# mainboard.net
KiCad netlist of a schematic drawn in EAGLE
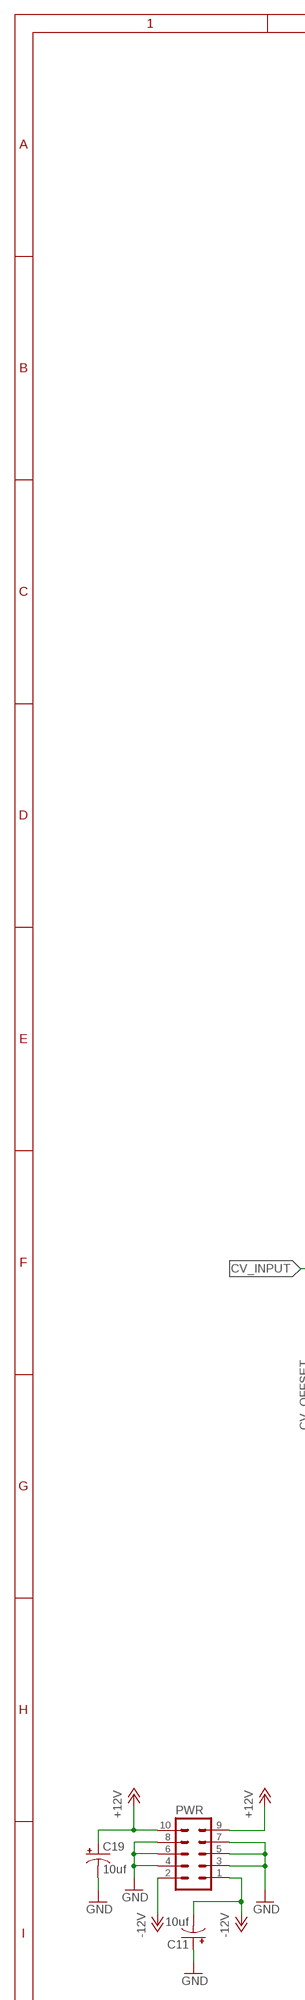
[diagram p0: schematic, sheet 1, part 1 of 2]
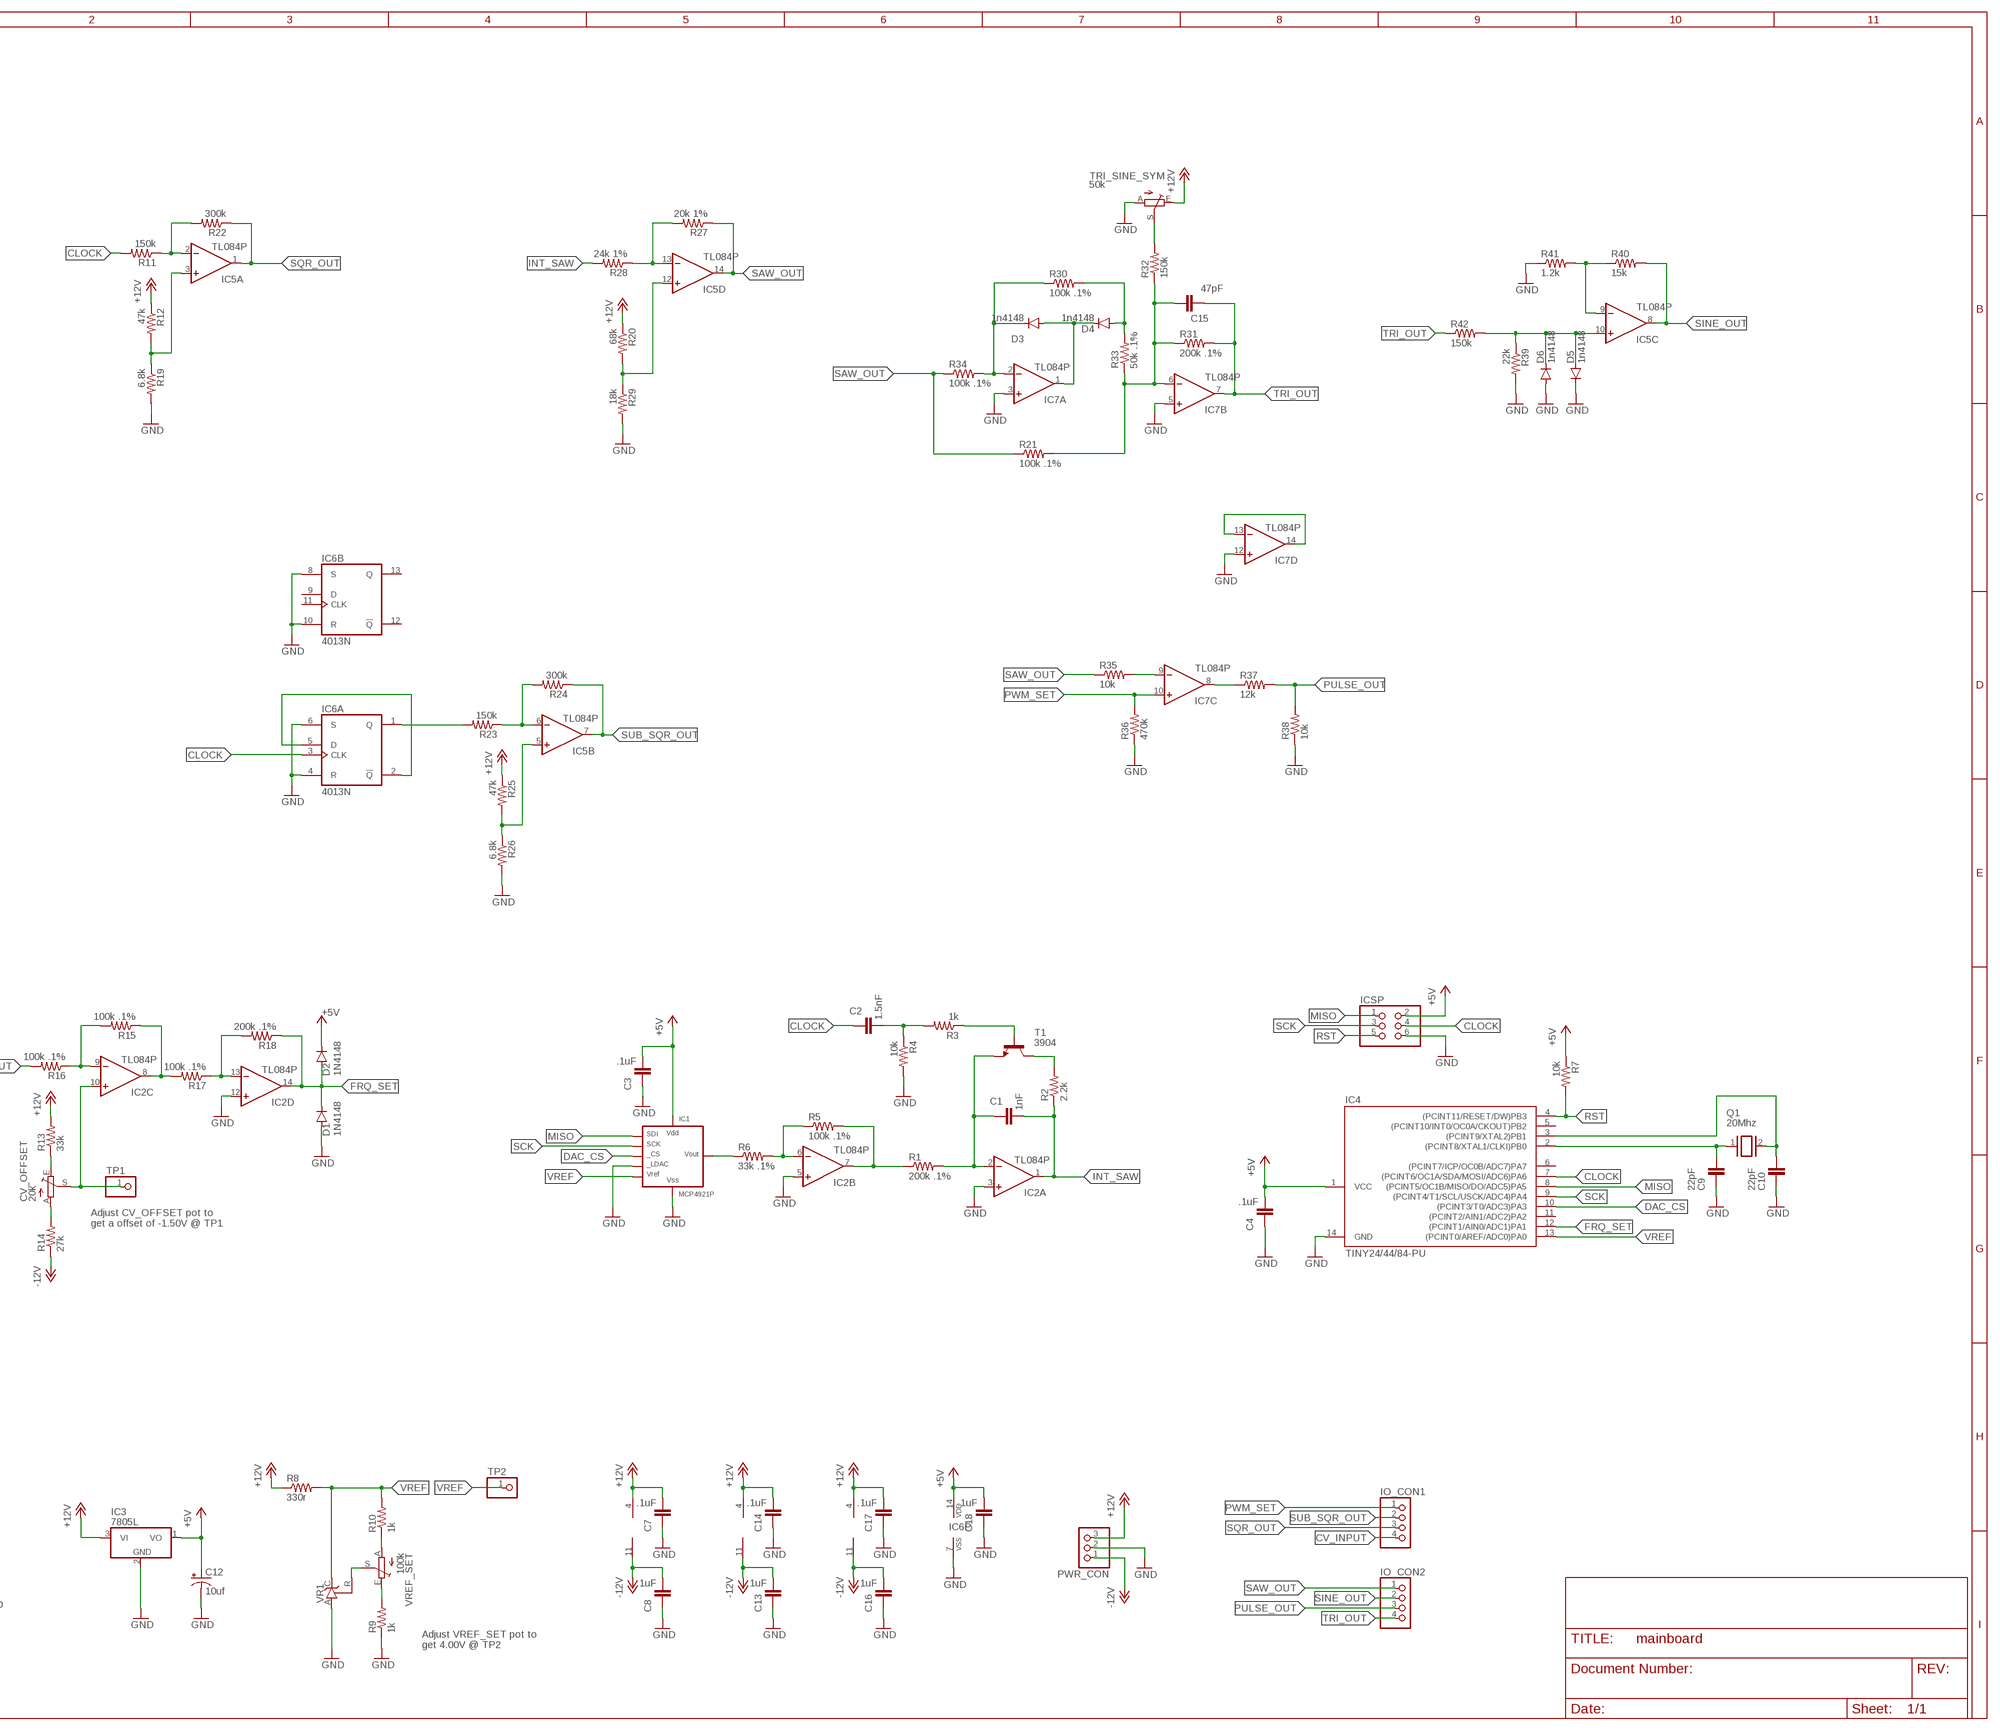
[diagram p1: schematic, sheet 1, part 2 of 2]

(export (version "E")
  (design (tool "Eeschema 10.0.6"))
  (components
    (comp (ref "C1")
      (value "1nF")
      (footprint "eagle-import:C050-025X075")
      (libsource (lib "eagle-import") (part "C-EU050-025X075"))
    )
    (comp (ref "C2")
      (value "1.5nF")
      (footprint "eagle-import:C050-024X044")
      (libsource (lib "eagle-import") (part "C-EU050-024X044"))
    )
    (comp (ref "C3")
      (value ".1uF")
      (footprint "eagle-import:C050-024X044")
      (libsource (lib "eagle-import") (part "C-EU050-024X044"))
    )
    (comp (ref "C4")
      (value ".1uF")
      (footprint "eagle-import:C050-024X044")
      (libsource (lib "eagle-import") (part "C-EU050-024X044"))
    )
    (comp (ref "C7")
      (value ".1uF")
      (footprint "eagle-import:C050-024X044")
      (libsource (lib "eagle-import") (part "C-EU050-024X044"))
    )
    (comp (ref "C8")
      (value ".1uF")
      (footprint "eagle-import:C050-024X044")
      (libsource (lib "eagle-import") (part "C-EU050-024X044"))
    )
    (comp (ref "C9")
      (value "22pF")
      (footprint "eagle-import:C050-024X044")
      (libsource (lib "eagle-import") (part "C-EU050-024X044"))
    )
    (comp (ref "C10")
      (value "22pF")
      (footprint "eagle-import:C050-024X044")
      (libsource (lib "eagle-import") (part "C-EU050-024X044"))
    )
    (comp (ref "C11")
      (value "10uf")
      (footprint "eagle-import:E2,5-5")
      (libsource (lib "eagle-import") (part "CPOL-USE2.5-5"))
    )
    (comp (ref "C12")
      (value "10uf")
      (footprint "eagle-import:E2,5-5")
      (libsource (lib "eagle-import") (part "CPOL-USE2.5-5"))
    )
    (comp (ref "C13")
      (value ".1uF")
      (footprint "eagle-import:C050-024X044")
      (libsource (lib "eagle-import") (part "C-EU050-024X044"))
    )
    (comp (ref "C14")
      (value ".1uF")
      (footprint "eagle-import:C050-024X044")
      (libsource (lib "eagle-import") (part "C-EU050-024X044"))
    )
    (comp (ref "C15")
      (value "47pF")
      (footprint "eagle-import:C050-024X044")
      (libsource (lib "eagle-import") (part "C-EU050-024X044"))
    )
    (comp (ref "C16")
      (value ".1uF")
      (footprint "eagle-import:C050-024X044")
      (libsource (lib "eagle-import") (part "C-EU050-024X044"))
    )
    (comp (ref "C17")
      (value ".1uF")
      (footprint "eagle-import:C050-024X044")
      (libsource (lib "eagle-import") (part "C-EU050-024X044"))
    )
    (comp (ref "C18")
      (value ".1uF")
      (footprint "eagle-import:C050-024X044")
      (libsource (lib "eagle-import") (part "C-EU050-024X044"))
    )
    (comp (ref "C19")
      (value "10uf")
      (footprint "eagle-import:E2,5-5")
      (libsource (lib "eagle-import") (part "CPOL-USE2.5-5"))
    )
    (comp (ref "CV_OFFSET")
      (value "20k")
      (footprint "eagle-import:S64YW")
      (libsource (lib "eagle-import") (part "TRIM_1234-S64YW"))
    )
    (comp (ref "D1")
      (value "1N4148")
      (footprint "eagle-import:DO35-7")
      (libsource (lib "eagle-import") (part "1N4148DO35-7"))
    )
    (comp (ref "D2")
      (value "1N4148")
      (footprint "eagle-import:DO35-7")
      (libsource (lib "eagle-import") (part "1N4148DO35-7"))
    )
    (comp (ref "D3")
      (value "1n4148")
      (footprint "eagle-import:DO35-7")
      (libsource (lib "eagle-import") (part "1N4148DO35-7"))
    )
    (comp (ref "D4")
      (value "1n4148")
      (footprint "eagle-import:DO35-7")
      (libsource (lib "eagle-import") (part "1N4148DO35-7"))
    )
    (comp (ref "D5")
      (value "1n4148")
      (footprint "eagle-import:DO35-7")
      (libsource (lib "eagle-import") (part "1N4148DO35-7"))
    )
    (comp (ref "D6")
      (value "1n4148")
      (footprint "eagle-import:DO35-7")
      (libsource (lib "eagle-import") (part "1N4148DO35-7"))
    )
    (comp (ref "IC1")
      (value "MCP4921P")
      (footprint "eagle-import:DIL8")
      (libsource (lib "eagle-import") (part "MCP4921P"))
    )
    (comp (ref "IC2")
      (value "TL084P")
      (footprint "eagle-import:DIL14")
      (libsource (lib "eagle-import") (part "TL084P"))
    )
    (comp (ref "IC3")
      (value "7805L")
      (footprint "eagle-import:TO92")
      (libsource (lib "eagle-import") (part "78L05"))
    )
    (comp (ref "IC4")
      (value "TINY24/44/84-PU")
      (footprint "eagle-import:DIL14")
      (libsource (lib "eagle-import") (part "TINY24/44/84-PU"))
    )
    (comp (ref "IC5")
      (value "TL084P")
      (footprint "eagle-import:DIL14")
      (libsource (lib "eagle-import") (part "TL084P"))
    )
    (comp (ref "IC6")
      (value "4013N")
      (footprint "eagle-import:DIL14")
      (libsource (lib "eagle-import") (part "4013N"))
    )
    (comp (ref "IC7")
      (value "TL084P")
      (footprint "eagle-import:DIL14")
      (libsource (lib "eagle-import") (part "TL084P"))
    )
    (comp (ref "ICSP")
      (value "PINHD-2X3")
      (footprint "eagle-import:2X03")
      (libsource (lib "eagle-import") (part "PINHD-2X3"))
    )
    (comp (ref "IO_CON1")
      (value "PINHD-1X4")
      (footprint "eagle-import:1X04")
      (libsource (lib "eagle-import") (part "PINHD-1X4"))
    )
    (comp (ref "IO_CON2")
      (value "PINHD-1X4")
      (footprint "eagle-import:1X04")
      (libsource (lib "eagle-import") (part "PINHD-1X4"))
    )
    (comp (ref "PWR")
      (value "ML10")
      (footprint "eagle-import:ML10")
      (libsource (lib "eagle-import") (part "ML10"))
    )
    (comp (ref "PWR_CON")
      (value "PINHD-1X3")
      (footprint "eagle-import:1X03")
      (libsource (lib "eagle-import") (part "PINHD-1X3"))
    )
    (comp (ref "Q1")
      (value "20Mhz")
      (footprint "eagle-import:QS")
      (libsource (lib "eagle-import") (part "XTAL/S"))
    )
    (comp (ref "R1")
      (value "200k .1%")
      (footprint "eagle-import:0207_7")
      (libsource (lib "eagle-import") (part "R-US_0207/7"))
    )
    (comp (ref "R2")
      (value "2.2k")
      (footprint "eagle-import:0207_7")
      (libsource (lib "eagle-import") (part "R-US_0207/7"))
    )
    (comp (ref "R3")
      (value "1k")
      (footprint "eagle-import:0207_7")
      (libsource (lib "eagle-import") (part "R-US_0207/7"))
    )
    (comp (ref "R4")
      (value "10k")
      (footprint "eagle-import:0207_7")
      (libsource (lib "eagle-import") (part "R-US_0207/7"))
    )
    (comp (ref "R5")
      (value "100k .1%")
      (footprint "eagle-import:0207_7")
      (libsource (lib "eagle-import") (part "R-US_0207/7"))
    )
    (comp (ref "R6")
      (value "33k .1%")
      (footprint "eagle-import:0207_7")
      (libsource (lib "eagle-import") (part "R-US_0207/7"))
    )
    (comp (ref "R7")
      (value "10k")
      (footprint "eagle-import:0207_7")
      (libsource (lib "eagle-import") (part "R-US_0207/7"))
    )
    (comp (ref "R8")
      (value "330r")
      (footprint "eagle-import:0207_7")
      (libsource (lib "eagle-import") (part "R-US_0207/7"))
    )
    (comp (ref "R9")
      (value "1k")
      (footprint "eagle-import:0207_7")
      (libsource (lib "eagle-import") (part "R-US_0207/7"))
    )
    (comp (ref "R10")
      (value "1k")
      (footprint "eagle-import:0207_7")
      (libsource (lib "eagle-import") (part "R-US_0207/7"))
    )
    (comp (ref "R11")
      (value "150k")
      (footprint "eagle-import:0207_7")
      (libsource (lib "eagle-import") (part "R-US_0207/7"))
    )
    (comp (ref "R12")
      (value "47k")
      (footprint "eagle-import:0207_7")
      (libsource (lib "eagle-import") (part "R-US_0207/7"))
    )
    (comp (ref "R13")
      (value "33k")
      (footprint "eagle-import:0207_7")
      (libsource (lib "eagle-import") (part "R-US_0207/7"))
    )
    (comp (ref "R14")
      (value "27k")
      (footprint "eagle-import:0207_7")
      (libsource (lib "eagle-import") (part "R-US_0207/7"))
    )
    (comp (ref "R15")
      (value "100k .1%")
      (footprint "eagle-import:0207_7")
      (libsource (lib "eagle-import") (part "R-US_0207/7"))
    )
    (comp (ref "R16")
      (value "100k .1%")
      (footprint "eagle-import:0207_7")
      (libsource (lib "eagle-import") (part "R-US_0207/7"))
    )
    (comp (ref "R17")
      (value "100k .1%")
      (footprint "eagle-import:0207_7")
      (libsource (lib "eagle-import") (part "R-US_0207/7"))
    )
    (comp (ref "R18")
      (value "200k .1%")
      (footprint "eagle-import:0207_7")
      (libsource (lib "eagle-import") (part "R-US_0207/7"))
    )
    (comp (ref "R19")
      (value "6.8k")
      (footprint "eagle-import:0207_7")
      (libsource (lib "eagle-import") (part "R-US_0207/7"))
    )
    (comp (ref "R20")
      (value "68k")
      (footprint "eagle-import:0207_7")
      (libsource (lib "eagle-import") (part "R-US_0207/7"))
    )
    (comp (ref "R21")
      (value "100k .1%")
      (footprint "eagle-import:0207_7")
      (libsource (lib "eagle-import") (part "R-US_0207/7"))
    )
    (comp (ref "R22")
      (value "300k")
      (footprint "eagle-import:0207_7")
      (libsource (lib "eagle-import") (part "R-US_0207/7"))
    )
    (comp (ref "R23")
      (value "150k")
      (footprint "eagle-import:0207_7")
      (libsource (lib "eagle-import") (part "R-US_0207/7"))
    )
    (comp (ref "R24")
      (value "300k")
      (footprint "eagle-import:0207_7")
      (libsource (lib "eagle-import") (part "R-US_0207/7"))
    )
    (comp (ref "R25")
      (value "47k")
      (footprint "eagle-import:0207_7")
      (libsource (lib "eagle-import") (part "R-US_0207/7"))
    )
    (comp (ref "R26")
      (value "6.8k")
      (footprint "eagle-import:0207_7")
      (libsource (lib "eagle-import") (part "R-US_0207/7"))
    )
    (comp (ref "R27")
      (value "20k 1%")
      (footprint "eagle-import:0207_7")
      (libsource (lib "eagle-import") (part "R-US_0207/7"))
    )
    (comp (ref "R28")
      (value "24k 1%")
      (footprint "eagle-import:0207_7")
      (libsource (lib "eagle-import") (part "R-US_0207/7"))
    )
    (comp (ref "R29")
      (value "18k")
      (footprint "eagle-import:0207_7")
      (libsource (lib "eagle-import") (part "R-US_0207/7"))
    )
    (comp (ref "R30")
      (value "100k .1%")
      (footprint "eagle-import:0207_7")
      (libsource (lib "eagle-import") (part "R-US_0207/7"))
    )
    (comp (ref "R31")
      (value "200k .1%")
      (footprint "eagle-import:0207_7")
      (libsource (lib "eagle-import") (part "R-US_0207/7"))
    )
    (comp (ref "R32")
      (value "150k")
      (footprint "eagle-import:0207_7")
      (libsource (lib "eagle-import") (part "R-US_0207/7"))
    )
    (comp (ref "R33")
      (value "50k .1%")
      (footprint "eagle-import:0207_7")
      (libsource (lib "eagle-import") (part "R-US_0207/7"))
    )
    (comp (ref "R34")
      (value "100k .1%")
      (footprint "eagle-import:0207_7")
      (libsource (lib "eagle-import") (part "R-US_0207/7"))
    )
    (comp (ref "R35")
      (value "10k")
      (footprint "eagle-import:0207_7")
      (libsource (lib "eagle-import") (part "R-US_0207/7"))
    )
    (comp (ref "R36")
      (value "470k")
      (footprint "eagle-import:0207_7")
      (libsource (lib "eagle-import") (part "R-US_0207/7"))
    )
    (comp (ref "R37")
      (value "12k")
      (footprint "eagle-import:0207_7")
      (libsource (lib "eagle-import") (part "R-US_0207/7"))
    )
    (comp (ref "R38")
      (value "10k")
      (footprint "eagle-import:0207_7")
      (libsource (lib "eagle-import") (part "R-US_0207/7"))
    )
    (comp (ref "R39")
      (value "22k")
      (footprint "eagle-import:0207_7")
      (libsource (lib "eagle-import") (part "R-US_0207/7"))
    )
    (comp (ref "R40")
      (value "15k")
      (footprint "eagle-import:0207_7")
      (libsource (lib "eagle-import") (part "R-US_0207/7"))
    )
    (comp (ref "R41")
      (value "1.2k")
      (footprint "eagle-import:0207_7")
      (libsource (lib "eagle-import") (part "R-US_0207/7"))
    )
    (comp (ref "R42")
      (value "150k")
      (footprint "eagle-import:0207_7")
      (libsource (lib "eagle-import") (part "R-US_0207/7"))
    )
    (comp (ref "T1")
      (value "3904")
      (footprint "eagle-import:TO92-EBC")
      (libsource (lib "eagle-import") (part "-NPN-TO92-EBC2N3904"))
    )
    (comp (ref "TP1")
      (value "PINHD-1X1")
      (footprint "eagle-import:1X01")
      (libsource (lib "eagle-import") (part "PINHD-1X1"))
    )
    (comp (ref "TP2")
      (value "PINHD-1X1")
      (footprint "eagle-import:1X01")
      (libsource (lib "eagle-import") (part "PINHD-1X1"))
    )
    (comp (ref "TRI_SINE_SYM")
      (value "50k")
      (footprint "eagle-import:S64YW")
      (libsource (lib "eagle-import") (part "TRIM_1234-S64YW"))
    )
    (comp (ref "VR1")
      (value "TL431CLP")
      (footprint "eagle-import:TO92-CLP")
      (libsource (lib "eagle-import") (part "TL431CLP"))
    )
    (comp (ref "VREF_SET")
      (value "100k")
      (footprint "eagle-import:S64YW")
      (libsource (lib "eagle-import") (part "TRIM_1234-S64YW"))
    )
  )
  (nets
    (net (code "1") (name "+5V") (class "Default")
      (node (ref "C12") (pin "+") (pinfunction "+_+") (pintype "passive"))
      (node (ref "C18") (pin "2") (pinfunction "2_2") (pintype "passive"))
      (node (ref "C3") (pin "2") (pinfunction "2_2") (pintype "passive"))
      (node (ref "C4") (pin "2") (pinfunction "2_2") (pintype "passive"))
      (node (ref "D2") (pin "C") (pinfunction "C_C") (pintype "passive"))
      (node (ref "IC1") (pin "1") (pinfunction "VDD_1") (pintype "power_in"))
      (node (ref "IC3") (pin "1") (pinfunction "VO_1") (pintype "passive"))
      (node (ref "IC4") (pin "1") (pinfunction "VCC_1") (pintype "power_in"))
      (node (ref "IC6") (pin "14") (pinfunction "VDD_14") (pintype "power_in"))
      (node (ref "ICSP") (pin "2") (pinfunction "2_2") (pintype "passive"))
      (node (ref "R7") (pin "1") (pinfunction "1_1") (pintype "passive"))
    )
    (net (code "2") (name "+12V") (class "Default")
      (node (ref "C14") (pin "2") (pinfunction "2_2") (pintype "passive"))
      (node (ref "C17") (pin "2") (pinfunction "2_2") (pintype "passive"))
      (node (ref "C19") (pin "+") (pinfunction "+_+") (pintype "passive"))
      (node (ref "C7") (pin "2") (pinfunction "2_2") (pintype "passive"))
      (node (ref "IC2") (pin "4") (pinfunction "V+_4") (pintype "power_in"))
      (node (ref "IC3") (pin "3") (pinfunction "VI_3") (pintype "input"))
      (node (ref "IC5") (pin "4") (pinfunction "V+_4") (pintype "power_in"))
      (node (ref "IC7") (pin "4") (pinfunction "V+_4") (pintype "power_in"))
      (node (ref "PWR") (pin "10") (pinfunction "10_10") (pintype "passive"))
      (node (ref "PWR") (pin "9") (pinfunction "9_9") (pintype "passive"))
      (node (ref "PWR_CON") (pin "3") (pinfunction "3_3") (pintype "passive"))
      (node (ref "R12") (pin "1") (pinfunction "1_1") (pintype "passive"))
      (node (ref "R13") (pin "2") (pinfunction "2_2") (pintype "passive"))
      (node (ref "R20") (pin "1") (pinfunction "1_1") (pintype "passive"))
      (node (ref "R25") (pin "1") (pinfunction "1_1") (pintype "passive"))
      (node (ref "R8") (pin "1") (pinfunction "1_1") (pintype "passive"))
      (node (ref "TRI_SINE_SYM") (pin "E") (pinfunction "E_E") (pintype "passive"))
    )
    (net (code "3") (name "-12V") (class "Default")
      (node (ref "C11") (pin "-") (pinfunction "-_-") (pintype "passive"))
      (node (ref "C13") (pin "2") (pinfunction "2_2") (pintype "passive"))
      (node (ref "C16") (pin "2") (pinfunction "2_2") (pintype "passive"))
      (node (ref "C8") (pin "2") (pinfunction "2_2") (pintype "passive"))
      (node (ref "IC2") (pin "11") (pinfunction "V-_11") (pintype "power_in"))
      (node (ref "IC5") (pin "11") (pinfunction "V-_11") (pintype "power_in"))
      (node (ref "IC7") (pin "11") (pinfunction "V-_11") (pintype "power_in"))
      (node (ref "PWR") (pin "1") (pinfunction "1_1") (pintype "passive"))
      (node (ref "PWR") (pin "2") (pinfunction "2_2") (pintype "passive"))
      (node (ref "PWR_CON") (pin "1") (pinfunction "1_1") (pintype "passive"))
      (node (ref "R14") (pin "1") (pinfunction "1_1") (pintype "passive"))
    )
    (net (code "4") (name "CLOCK") (class "Default")
      (node (ref "C2") (pin "1") (pinfunction "1_1") (pintype "passive"))
      (node (ref "IC4") (pin "7") (pinfunction "(PCINT6/OC1A/SDA/MOSI/ADC6)PA6_7") (pintype "bidirectional"))
      (node (ref "IC6") (pin "3") (pinfunction "CLK_3") (pintype "input"))
      (node (ref "ICSP") (pin "4") (pinfunction "4_4") (pintype "passive"))
      (node (ref "R11") (pin "2") (pinfunction "2_2") (pintype "passive"))
    )
    (net (code "5") (name "CV_INPUT") (class "Default")
      (node (ref "IO_CON1") (pin "4") (pinfunction "4_4") (pintype "passive"))
      (node (ref "R16") (pin "2") (pinfunction "2_2") (pintype "passive"))
    )
    (net (code "6") (name "DAC_CS") (class "Default")
      (node (ref "IC1") (pin "2") (pinfunction "CS_2") (pintype "input"))
      (node (ref "IC4") (pin "10") (pinfunction "(PCINT3/T0/ADC3)PA3_10") (pintype "bidirectional"))
    )
    (net (code "7") (name "FRQ_SET") (class "Default")
      (node (ref "D1") (pin "C") (pinfunction "C_C") (pintype "passive"))
      (node (ref "D2") (pin "A") (pinfunction "A_A") (pintype "passive"))
      (node (ref "IC2") (pin "14") (pinfunction "OUT_14") (pintype "output"))
      (node (ref "IC4") (pin "12") (pinfunction "(PCINT1/AIN0/ADC1)PA1_12") (pintype "bidirectional"))
      (node (ref "R18") (pin "1") (pinfunction "1_1") (pintype "passive"))
    )
    (net (code "8") (name "GND") (class "Default")
      (node (ref "C10") (pin "1") (pinfunction "1_1") (pintype "passive"))
      (node (ref "C11") (pin "+") (pinfunction "+_+") (pintype "passive"))
      (node (ref "C12") (pin "-") (pinfunction "-_-") (pintype "passive"))
      (node (ref "C13") (pin "1") (pinfunction "1_1") (pintype "passive"))
      (node (ref "C14") (pin "1") (pinfunction "1_1") (pintype "passive"))
      (node (ref "C16") (pin "1") (pinfunction "1_1") (pintype "passive"))
      (node (ref "C17") (pin "1") (pinfunction "1_1") (pintype "passive"))
      (node (ref "C18") (pin "1") (pinfunction "1_1") (pintype "passive"))
      (node (ref "C19") (pin "-") (pinfunction "-_-") (pintype "passive"))
      (node (ref "C3") (pin "1") (pinfunction "1_1") (pintype "passive"))
      (node (ref "C4") (pin "1") (pinfunction "1_1") (pintype "passive"))
      (node (ref "C7") (pin "1") (pinfunction "1_1") (pintype "passive"))
      (node (ref "C8") (pin "1") (pinfunction "1_1") (pintype "passive"))
      (node (ref "C9") (pin "1") (pinfunction "1_1") (pintype "passive"))
      (node (ref "D1") (pin "A") (pinfunction "A_A") (pintype "passive"))
      (node (ref "D5") (pin "C") (pinfunction "C_C") (pintype "passive"))
      (node (ref "D6") (pin "A") (pinfunction "A_A") (pintype "passive"))
      (node (ref "IC1") (pin "5") (pinfunction "LDAC_5") (pintype "input"))
      (node (ref "IC1") (pin "7") (pinfunction "VSS_7") (pintype "power_in"))
      (node (ref "IC2") (pin "12") (pinfunction "+IN_12") (pintype "input"))
      (node (ref "IC2") (pin "3") (pinfunction "+IN_3") (pintype "input"))
      (node (ref "IC2") (pin "5") (pinfunction "+IN_5") (pintype "input"))
      (node (ref "IC3") (pin "2") (pinfunction "GND_2") (pintype "passive"))
      (node (ref "IC4") (pin "14") (pinfunction "GND_14") (pintype "power_in"))
      (node (ref "IC6") (pin "10") (pinfunction "R_10") (pintype "input"))
      (node (ref "IC6") (pin "4") (pinfunction "R_4") (pintype "input"))
      (node (ref "IC6") (pin "6") (pinfunction "S_6") (pintype "input"))
      (node (ref "IC6") (pin "7") (pinfunction "VSS_7") (pintype "power_in"))
      (node (ref "IC6") (pin "8") (pinfunction "S_8") (pintype "input"))
      (node (ref "IC7") (pin "12") (pinfunction "+IN_12") (pintype "input"))
      (node (ref "IC7") (pin "3") (pinfunction "+IN_3") (pintype "input"))
      (node (ref "IC7") (pin "5") (pinfunction "+IN_5") (pintype "input"))
      (node (ref "ICSP") (pin "6") (pinfunction "6_6") (pintype "passive"))
      (node (ref "PWR") (pin "3") (pinfunction "3_3") (pintype "passive"))
      (node (ref "PWR") (pin "4") (pinfunction "4_4") (pintype "passive"))
      (node (ref "PWR") (pin "5") (pinfunction "5_5") (pintype "passive"))
      (node (ref "PWR") (pin "6") (pinfunction "6_6") (pintype "passive"))
      (node (ref "PWR") (pin "7") (pinfunction "7_7") (pintype "passive"))
      (node (ref "PWR") (pin "8") (pinfunction "8_8") (pintype "passive"))
      (node (ref "PWR_CON") (pin "2") (pinfunction "2_2") (pintype "passive"))
      (node (ref "R19") (pin "2") (pinfunction "2_2") (pintype "passive"))
      (node (ref "R26") (pin "2") (pinfunction "2_2") (pintype "passive"))
      (node (ref "R29") (pin "2") (pinfunction "2_2") (pintype "passive"))
      (node (ref "R36") (pin "1") (pinfunction "1_1") (pintype "passive"))
      (node (ref "R38") (pin "1") (pinfunction "1_1") (pintype "passive"))
      (node (ref "R39") (pin "2") (pinfunction "2_2") (pintype "passive"))
      (node (ref "R4") (pin "2") (pinfunction "2_2") (pintype "passive"))
      (node (ref "R41") (pin "1") (pinfunction "1_1") (pintype "passive"))
      (node (ref "R9") (pin "1") (pinfunction "1_1") (pintype "passive"))
      (node (ref "TRI_SINE_SYM") (pin "A") (pinfunction "A_A") (pintype "passive"))
      (node (ref "VR1") (pin "A") (pinfunction "A_A") (pintype "passive"))
    )
    (net (code "9") (name "INT_SAW") (class "Default")
      (node (ref "C1") (pin "2") (pinfunction "2_2") (pintype "passive"))
      (node (ref "IC2") (pin "1") (pinfunction "OUT_1") (pintype "output"))
      (node (ref "R2") (pin "1") (pinfunction "1_1") (pintype "passive"))
      (node (ref "R28") (pin "2") (pinfunction "2_2") (pintype "passive"))
    )
    (net (code "10") (name "MISO") (class "Default")
      (node (ref "IC1") (pin "4") (pinfunction "SDI_4") (pintype "input"))
      (node (ref "IC4") (pin "8") (pinfunction "(PCINT5/OC1B/MISO/DO/ADC5)PA5_8") (pintype "bidirectional"))
      (node (ref "ICSP") (pin "1") (pinfunction "1_1") (pintype "passive"))
    )
    (net (code "11") (name "Net-(C2-Pad2)") (class "Default")
      (node (ref "C2") (pin "2") (pinfunction "2_2") (pintype "passive"))
      (node (ref "R3") (pin "2") (pinfunction "2_2") (pintype "passive"))
      (node (ref "R4") (pin "1") (pinfunction "1_1") (pintype "passive"))
    )
    (net (code "12") (name "Net-(CV_OFFSET-PadA)") (class "Default")
      (node (ref "CV_OFFSET") (pin "A") (pinfunction "A_A") (pintype "passive"))
      (node (ref "R14") (pin "2") (pinfunction "2_2") (pintype "passive"))
    )
    (net (code "13") (name "Net-(CV_OFFSET-PadE)") (class "Default")
      (node (ref "CV_OFFSET") (pin "E") (pinfunction "E_E") (pintype "passive"))
      (node (ref "R13") (pin "1") (pinfunction "1_1") (pintype "passive"))
    )
    (net (code "14") (name "Net-(D4-PadA)") (class "Default")
      (node (ref "D4") (pin "A") (pinfunction "A_A") (pintype "passive"))
      (node (ref "R30") (pin "2") (pinfunction "2_2") (pintype "passive"))
      (node (ref "R33") (pin "2") (pinfunction "2_2") (pintype "passive"))
    )
    (net (code "15") (name "Net-(IC1-VOUT)") (class "Default")
      (node (ref "IC1") (pin "8") (pinfunction "VOUT_8") (pintype "output"))
      (node (ref "R6") (pin "1") (pinfunction "1_1") (pintype "passive"))
    )
    (net (code "16") (name "Net-(IC2A--IN)") (class "Default")
      (node (ref "C1") (pin "1") (pinfunction "1_1") (pintype "passive"))
      (node (ref "IC2") (pin "2") (pinfunction "-IN_2") (pintype "input"))
      (node (ref "R1") (pin "2") (pinfunction "2_2") (pintype "passive"))
      (node (ref "T1") (pin "E") (pinfunction "E_E") (pintype "passive"))
    )
    (net (code "17") (name "Net-(IC2B--IN)") (class "Default")
      (node (ref "IC2") (pin "6") (pinfunction "-IN_6") (pintype "input"))
      (node (ref "R5") (pin "1") (pinfunction "1_1") (pintype "passive"))
      (node (ref "R6") (pin "2") (pinfunction "2_2") (pintype "passive"))
    )
    (net (code "18") (name "Net-(IC2B-OUT)") (class "Default")
      (node (ref "IC2") (pin "7") (pinfunction "OUT_7") (pintype "output"))
      (node (ref "R1") (pin "1") (pinfunction "1_1") (pintype "passive"))
      (node (ref "R5") (pin "2") (pinfunction "2_2") (pintype "passive"))
    )
    (net (code "19") (name "Net-(IC2C-+IN)") (class "Default")
      (node (ref "CV_OFFSET") (pin "S") (pinfunction "S_S") (pintype "passive"))
      (node (ref "IC2") (pin "10") (pinfunction "+IN_10") (pintype "input"))
      (node (ref "TP1") (pin "1") (pinfunction "1_1") (pintype "passive"))
    )
    (net (code "20") (name "Net-(IC2C--IN)") (class "Default")
      (node (ref "IC2") (pin "9") (pinfunction "-IN_9") (pintype "input"))
      (node (ref "R15") (pin "2") (pinfunction "2_2") (pintype "passive"))
      (node (ref "R16") (pin "1") (pinfunction "1_1") (pintype "passive"))
    )
    (net (code "21") (name "Net-(IC2C-OUT)") (class "Default")
      (node (ref "IC2") (pin "8") (pinfunction "OUT_8") (pintype "output"))
      (node (ref "R15") (pin "1") (pinfunction "1_1") (pintype "passive"))
      (node (ref "R17") (pin "2") (pinfunction "2_2") (pintype "passive"))
    )
    (net (code "22") (name "Net-(IC2D--IN)") (class "Default")
      (node (ref "IC2") (pin "13") (pinfunction "-IN_13") (pintype "input"))
      (node (ref "R17") (pin "1") (pinfunction "1_1") (pintype "passive"))
      (node (ref "R18") (pin "2") (pinfunction "2_2") (pintype "passive"))
    )
    (net (code "23") (name "Net-(IC4-(PCINT8{slash}XTAL1{slash}CLKI)PB0)") (class "Default")
      (node (ref "C9") (pin "2") (pinfunction "2_2") (pintype "passive"))
      (node (ref "IC4") (pin "2") (pinfunction "(PCINT8/XTAL1/CLKI)PB0_2") (pintype "bidirectional"))
      (node (ref "Q1") (pin "1") (pinfunction "1_1") (pintype "passive"))
    )
    (net (code "24") (name "Net-(IC4-(PCINT9{slash}XTAL2)PB1)") (class "Default")
      (node (ref "C10") (pin "2") (pinfunction "2_2") (pintype "passive"))
      (node (ref "IC4") (pin "3") (pinfunction "(PCINT9/XTAL2)PB1_3") (pintype "bidirectional"))
      (node (ref "Q1") (pin "2") (pinfunction "2_2") (pintype "passive"))
    )
    (net (code "25") (name "Net-(IC5A-+IN)") (class "Default")
      (node (ref "IC5") (pin "3") (pinfunction "+IN_3") (pintype "input"))
      (node (ref "R12") (pin "2") (pinfunction "2_2") (pintype "passive"))
      (node (ref "R19") (pin "1") (pinfunction "1_1") (pintype "passive"))
    )
    (net (code "26") (name "Net-(IC5A--IN)") (class "Default")
      (node (ref "IC5") (pin "2") (pinfunction "-IN_2") (pintype "input"))
      (node (ref "R11") (pin "1") (pinfunction "1_1") (pintype "passive"))
      (node (ref "R22") (pin "2") (pinfunction "2_2") (pintype "passive"))
    )
    (net (code "27") (name "Net-(IC5B-+IN)") (class "Default")
      (node (ref "IC5") (pin "5") (pinfunction "+IN_5") (pintype "input"))
      (node (ref "R25") (pin "2") (pinfunction "2_2") (pintype "passive"))
      (node (ref "R26") (pin "1") (pinfunction "1_1") (pintype "passive"))
    )
    (net (code "28") (name "Net-(IC5B--IN)") (class "Default")
      (node (ref "IC5") (pin "6") (pinfunction "-IN_6") (pintype "input"))
      (node (ref "R23") (pin "1") (pinfunction "1_1") (pintype "passive"))
      (node (ref "R24") (pin "2") (pinfunction "2_2") (pintype "passive"))
    )
    (net (code "29") (name "Net-(IC5C-+IN)") (class "Default")
      (node (ref "D5") (pin "A") (pinfunction "A_A") (pintype "passive"))
      (node (ref "D6") (pin "C") (pinfunction "C_C") (pintype "passive"))
      (node (ref "IC5") (pin "10") (pinfunction "+IN_10") (pintype "input"))
      (node (ref "R39") (pin "1") (pinfunction "1_1") (pintype "passive"))
      (node (ref "R42") (pin "2") (pinfunction "2_2") (pintype "passive"))
    )
    (net (code "30") (name "Net-(IC5C--IN)") (class "Default")
      (node (ref "IC5") (pin "9") (pinfunction "-IN_9") (pintype "input"))
      (node (ref "R40") (pin "1") (pinfunction "1_1") (pintype "passive"))
      (node (ref "R41") (pin "2") (pinfunction "2_2") (pintype "passive"))
    )
    (net (code "31") (name "Net-(IC5D-+IN)") (class "Default")
      (node (ref "IC5") (pin "12") (pinfunction "+IN_12") (pintype "input"))
      (node (ref "R20") (pin "2") (pinfunction "2_2") (pintype "passive"))
      (node (ref "R29") (pin "1") (pinfunction "1_1") (pintype "passive"))
    )
    (net (code "32") (name "Net-(IC5D--IN)") (class "Default")
      (node (ref "IC5") (pin "13") (pinfunction "-IN_13") (pintype "input"))
      (node (ref "R27") (pin "2") (pinfunction "2_2") (pintype "passive"))
      (node (ref "R28") (pin "1") (pinfunction "1_1") (pintype "passive"))
    )
    (net (code "33") (name "Net-(IC6A-D)") (class "Default")
      (node (ref "IC6") (pin "2") (pinfunction "~{Q}_2") (pintype "output"))
      (node (ref "IC6") (pin "5") (pinfunction "D_5") (pintype "input"))
    )
    (net (code "34") (name "Net-(IC6A-Q)") (class "Default")
      (node (ref "IC6") (pin "1") (pinfunction "Q_1") (pintype "output"))
      (node (ref "R23") (pin "2") (pinfunction "2_2") (pintype "passive"))
    )
    (net (code "35") (name "Net-(IC7A--IN)") (class "Default")
      (node (ref "D3") (pin "C") (pinfunction "C_C") (pintype "passive"))
      (node (ref "IC7") (pin "2") (pinfunction "-IN_2") (pintype "input"))
      (node (ref "R30") (pin "1") (pinfunction "1_1") (pintype "passive"))
      (node (ref "R34") (pin "2") (pinfunction "2_2") (pintype "passive"))
    )
    (net (code "36") (name "Net-(IC7A-OUT)") (class "Default")
      (node (ref "D3") (pin "A") (pinfunction "A_A") (pintype "passive"))
      (node (ref "D4") (pin "C") (pinfunction "C_C") (pintype "passive"))
      (node (ref "IC7") (pin "1") (pinfunction "OUT_1") (pintype "output"))
    )
    (net (code "37") (name "Net-(IC7B--IN)") (class "Default")
      (node (ref "C15") (pin "2") (pinfunction "2_2") (pintype "passive"))
      (node (ref "IC7") (pin "6") (pinfunction "-IN_6") (pintype "input"))
      (node (ref "R21") (pin "2") (pinfunction "2_2") (pintype "passive"))
      (node (ref "R31") (pin "1") (pinfunction "1_1") (pintype "passive"))
      (node (ref "R32") (pin "1") (pinfunction "1_1") (pintype "passive"))
      (node (ref "R33") (pin "1") (pinfunction "1_1") (pintype "passive"))
    )
    (net (code "38") (name "Net-(IC7C--IN)") (class "Default")
      (node (ref "IC7") (pin "9") (pinfunction "-IN_9") (pintype "input"))
      (node (ref "R35") (pin "2") (pinfunction "2_2") (pintype "passive"))
    )
    (net (code "39") (name "Net-(IC7C-OUT)") (class "Default")
      (node (ref "IC7") (pin "8") (pinfunction "OUT_8") (pintype "output"))
      (node (ref "R37") (pin "1") (pinfunction "1_1") (pintype "passive"))
    )
    (net (code "40") (name "Net-(IC7D--IN)") (class "Default")
      (node (ref "IC7") (pin "13") (pinfunction "-IN_13") (pintype "input"))
      (node (ref "IC7") (pin "14") (pinfunction "OUT_14") (pintype "output"))
    )
    (net (code "41") (name "Net-(R2-Pad2)") (class "Default")
      (node (ref "R2") (pin "2") (pinfunction "2_2") (pintype "passive"))
      (node (ref "T1") (pin "C") (pinfunction "C_C") (pintype "passive"))
    )
    (net (code "42") (name "Net-(R3-Pad1)") (class "Default")
      (node (ref "R3") (pin "1") (pinfunction "1_1") (pintype "passive"))
      (node (ref "T1") (pin "B") (pinfunction "B_B") (pintype "passive"))
    )
    (net (code "43") (name "Net-(R9-Pad2)") (class "Default")
      (node (ref "R9") (pin "2") (pinfunction "2_2") (pintype "passive"))
      (node (ref "VREF_SET") (pin "E") (pinfunction "E_E") (pintype "passive"))
    )
    (net (code "44") (name "Net-(R10-Pad1)") (class "Default")
      (node (ref "R10") (pin "1") (pinfunction "1_1") (pintype "passive"))
      (node (ref "VREF_SET") (pin "A") (pinfunction "A_A") (pintype "passive"))
    )
    (net (code "45") (name "Net-(R32-Pad2)") (class "Default")
      (node (ref "R32") (pin "2") (pinfunction "2_2") (pintype "passive"))
      (node (ref "TRI_SINE_SYM") (pin "S") (pinfunction "S_S") (pintype "passive"))
    )
    (net (code "46") (name "Net-(VR1-PadR)") (class "Default")
      (node (ref "VR1") (pin "R") (pinfunction "R_R") (pintype "passive"))
      (node (ref "VREF_SET") (pin "S") (pinfunction "S_S") (pintype "passive"))
    )
    (net (code "47") (name "PULSE_OUT") (class "Default")
      (node (ref "IO_CON2") (pin "3") (pinfunction "3_3") (pintype "passive"))
      (node (ref "R37") (pin "2") (pinfunction "2_2") (pintype "passive"))
      (node (ref "R38") (pin "2") (pinfunction "2_2") (pintype "passive"))
    )
    (net (code "48") (name "PWM_SET") (class "Default")
      (node (ref "IC7") (pin "10") (pinfunction "+IN_10") (pintype "input"))
      (node (ref "IO_CON1") (pin "1") (pinfunction "1_1") (pintype "passive"))
      (node (ref "R36") (pin "2") (pinfunction "2_2") (pintype "passive"))
    )
    (net (code "49") (name "RST") (class "Default")
      (node (ref "IC4") (pin "4") (pinfunction "(PCINT11/RESET/DW)PB3_4") (pintype "bidirectional"))
      (node (ref "ICSP") (pin "5") (pinfunction "5_5") (pintype "passive"))
      (node (ref "R7") (pin "2") (pinfunction "2_2") (pintype "passive"))
    )
    (net (code "50") (name "SAW_OUT") (class "Default")
      (node (ref "IC5") (pin "14") (pinfunction "OUT_14") (pintype "output"))
      (node (ref "IO_CON2") (pin "1") (pinfunction "1_1") (pintype "passive"))
      (node (ref "R21") (pin "1") (pinfunction "1_1") (pintype "passive"))
      (node (ref "R27") (pin "1") (pinfunction "1_1") (pintype "passive"))
      (node (ref "R34") (pin "1") (pinfunction "1_1") (pintype "passive"))
      (node (ref "R35") (pin "1") (pinfunction "1_1") (pintype "passive"))
    )
    (net (code "51") (name "SCK") (class "Default")
      (node (ref "IC1") (pin "3") (pinfunction "SCK_3") (pintype "input"))
      (node (ref "IC4") (pin "9") (pinfunction "(PCINT4/T1/SCL/USCK/ADC4)PA4_9") (pintype "bidirectional"))
      (node (ref "ICSP") (pin "3") (pinfunction "3_3") (pintype "passive"))
    )
    (net (code "52") (name "SINE_OUT") (class "Default")
      (node (ref "IC5") (pin "8") (pinfunction "OUT_8") (pintype "output"))
      (node (ref "IO_CON2") (pin "2") (pinfunction "2_2") (pintype "passive"))
      (node (ref "R40") (pin "2") (pinfunction "2_2") (pintype "passive"))
    )
    (net (code "53") (name "SQR_OUT") (class "Default")
      (node (ref "IC5") (pin "1") (pinfunction "OUT_1") (pintype "output"))
      (node (ref "IO_CON1") (pin "3") (pinfunction "3_3") (pintype "passive"))
      (node (ref "R22") (pin "1") (pinfunction "1_1") (pintype "passive"))
    )
    (net (code "54") (name "SUB_SQR_OUT") (class "Default")
      (node (ref "IC5") (pin "7") (pinfunction "OUT_7") (pintype "output"))
      (node (ref "IO_CON1") (pin "2") (pinfunction "2_2") (pintype "passive"))
      (node (ref "R24") (pin "1") (pinfunction "1_1") (pintype "passive"))
    )
    (net (code "55") (name "TRI_OUT") (class "Default")
      (node (ref "C15") (pin "1") (pinfunction "1_1") (pintype "passive"))
      (node (ref "IC7") (pin "7") (pinfunction "OUT_7") (pintype "output"))
      (node (ref "IO_CON2") (pin "4") (pinfunction "4_4") (pintype "passive"))
      (node (ref "R31") (pin "2") (pinfunction "2_2") (pintype "passive"))
      (node (ref "R42") (pin "1") (pinfunction "1_1") (pintype "passive"))
    )
    (net (code "56") (name "VREF") (class "Default")
      (node (ref "IC1") (pin "6") (pinfunction "VREF_6") (pintype "input"))
      (node (ref "IC4") (pin "13") (pinfunction "(PCINT0/AREF/ADC0)PA0_13") (pintype "bidirectional"))
      (node (ref "R10") (pin "2") (pinfunction "2_2") (pintype "passive"))
      (node (ref "R8") (pin "2") (pinfunction "2_2") (pintype "passive"))
      (node (ref "TP2") (pin "1") (pinfunction "1_1") (pintype "passive"))
      (node (ref "VR1") (pin "C") (pinfunction "C_C") (pintype "passive"))
    )
    (net (code "57") (name "unconnected-(CV_OFFSET-S-PadS@1)") (class "Default")
      (node (ref "CV_OFFSET") (pin "S@1") (pinfunction "S_S@1") (pintype "passive"))
    )
    (net (code "58") (name "unconnected-(IC4-(PCINT2{slash}AIN1{slash}ADC2)PA2-Pad11)") (class "Default")
      (node (ref "IC4") (pin "11") (pinfunction "(PCINT2/AIN1/ADC2)PA2_11") (pintype "bidirectional"))
    )
    (net (code "59") (name "unconnected-(IC4-(PCINT7{slash}ICP{slash}OC0B{slash}ADC7)PA7-Pad6)") (class "Default")
      (node (ref "IC4") (pin "6") (pinfunction "(PCINT7/ICP/OC0B/ADC7)PA7_6") (pintype "bidirectional"))
    )
    (net (code "60") (name "unconnected-(IC4-(PCINT10{slash}INT0{slash}OC0A{slash}CKOUT)PB2-Pad5)") (class "Default")
      (node (ref "IC4") (pin "5") (pinfunction "(PCINT10/INT0/OC0A/CKOUT)PB2_5") (pintype "bidirectional"))
    )
    (net (code "61") (name "unconnected-(IC6B-CLK-Pad11)") (class "Default")
      (node (ref "IC6") (pin "11") (pinfunction "CLK_11") (pintype "input"))
    )
    (net (code "62") (name "unconnected-(IC6B-D-Pad9)") (class "Default")
      (node (ref "IC6") (pin "9") (pinfunction "D_9") (pintype "input"))
    )
    (net (code "63") (name "unconnected-(IC6B-Q-Pad13)") (class "Default")
      (node (ref "IC6") (pin "13") (pinfunction "Q_13") (pintype "output"))
    )
    (net (code "64") (name "unconnected-(IC6B-~{Q}-Pad12)") (class "Default")
      (node (ref "IC6") (pin "12") (pinfunction "~{Q}_12") (pintype "output"))
    )
    (net (code "65") (name "unconnected-(TRI_SINE_SYM-S-PadS@1)") (class "Default")
      (node (ref "TRI_SINE_SYM") (pin "S@1") (pinfunction "S_S@1") (pintype "passive"))
    )
    (net (code "66") (name "unconnected-(VREF_SET-S-PadS@1)") (class "Default")
      (node (ref "VREF_SET") (pin "S@1") (pinfunction "S_S@1") (pintype "passive"))
    )
  )
)
